# Motor_Controller_Adapter_Board_rev1.net
KiCad netlist of a schematic drawn in EAGLE
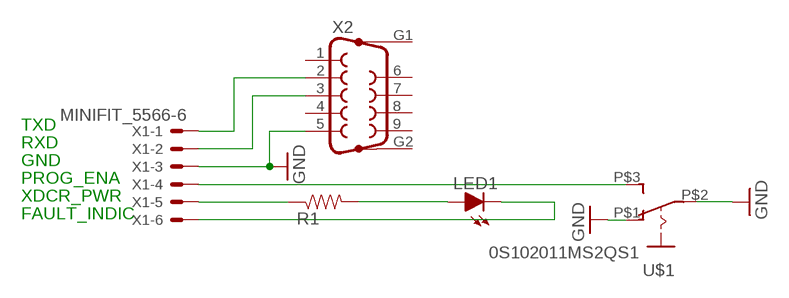
[diagram p0: schematic, sheet 1]

(export (version "E")
  (design (tool "Eeschema 10.0.6"))
  (components
    (comp (ref "LED1")
      (value "LED-0805")
      (footprint "eagle-import:LED-805")
      (libsource (lib "eagle-import") (part "LED-0805"))
    )
    (comp (ref "R1")
      (value "RESISTOR0805-RES")
      (footprint "eagle-import:0805")
      (libsource (lib "eagle-import") (part "RESISTOR0805-RES"))
    )
    (comp (ref "U$1")
      (value "0S102011MS2QS1")
      (footprint "eagle-import:0S102011MS2QS1")
      (libsource (lib "eagle-import") (part "0S102011MS2QS1"))
    )
    (comp (ref "X1")
      (value "MINIFIT_5566-6")
      (footprint "eagle-import:MINIFIT_5566-6")
      (fields (field (name "MPN") "95566-61002"))
      (libsource (lib "eagle-import") (part "MINIFIT_5566-6"))
    )
    (comp (ref "X2")
      (value "F09HP")
      (footprint "eagle-import:F09HP")
      (libsource (lib "eagle-import") (part "F09HP"))
    )
  )
  (nets
    (net (code "1") (name "GND") (class "Default")
      (node (ref "U$1") (pin "P$1") (pinfunction "O_P$1") (pintype "passive"))
      (node (ref "U$1") (pin "P$2") (pinfunction "P_P$2") (pintype "passive"))
      (node (ref "X1") (pin "3") (pinfunction "S_3") (pintype "passive"))
      (node (ref "X2") (pin "5") (pinfunction "5_5") (pintype "passive"))
    )
    (net (code "2") (name "Net-(LED1-PadA)") (class "Default")
      (node (ref "LED1") (pin "A") (pinfunction "A_A") (pintype "passive"))
      (node (ref "R1") (pin "2") (pinfunction "2_2") (pintype "passive"))
    )
    (net (code "3") (name "Net-(U$1-S)") (class "Default")
      (node (ref "U$1") (pin "P$3") (pinfunction "S_P$3") (pintype "passive"))
      (node (ref "X1") (pin "4") (pinfunction "S_4") (pintype "passive"))
    )
    (net (code "4") (name "Net-(X1A-S)") (class "Default")
      (node (ref "X1") (pin "1") (pinfunction "S_1") (pintype "passive"))
      (node (ref "X2") (pin "2") (pinfunction "2_2") (pintype "passive"))
    )
    (net (code "5") (name "Net-(X1B-S)") (class "Default")
      (node (ref "X1") (pin "2") (pinfunction "S_2") (pintype "passive"))
      (node (ref "X2") (pin "3") (pinfunction "3_3") (pintype "passive"))
    )
    (net (code "6") (name "Net-(X1E-S)") (class "Default")
      (node (ref "R1") (pin "1") (pinfunction "1_1") (pintype "passive"))
      (node (ref "X1") (pin "5") (pinfunction "S_5") (pintype "passive"))
    )
    (net (code "7") (name "Net-(X1F-S)") (class "Default")
      (node (ref "LED1") (pin "C") (pinfunction "C_C") (pintype "passive"))
      (node (ref "X1") (pin "6") (pinfunction "S_6") (pintype "passive"))
    )
    (net (code "8") (name "unconnected-(X2-Pad1)") (class "Default")
      (node (ref "X2") (pin "1") (pinfunction "1_1") (pintype "passive"))
    )
    (net (code "9") (name "unconnected-(X2-Pad4)") (class "Default")
      (node (ref "X2") (pin "4") (pinfunction "4_4") (pintype "passive"))
    )
    (net (code "10") (name "unconnected-(X2-Pad6)") (class "Default")
      (node (ref "X2") (pin "6") (pinfunction "6_6") (pintype "passive"))
    )
    (net (code "11") (name "unconnected-(X2-Pad7)") (class "Default")
      (node (ref "X2") (pin "7") (pinfunction "7_7") (pintype "passive"))
    )
    (net (code "12") (name "unconnected-(X2-Pad8)") (class "Default")
      (node (ref "X2") (pin "8") (pinfunction "8_8") (pintype "passive"))
    )
    (net (code "13") (name "unconnected-(X2-Pad9)") (class "Default")
      (node (ref "X2") (pin "9") (pinfunction "9_9") (pintype "passive"))
    )
    (net (code "14") (name "unconnected-(X2-PadG1)") (class "Default")
      (node (ref "X2") (pin "G1") (pinfunction "G1_G1") (pintype "passive"))
    )
    (net (code "15") (name "unconnected-(X2-PadG2)") (class "Default")
      (node (ref "X2") (pin "G2") (pinfunction "G2_G2") (pintype "passive"))
    )
  )
)
